# DIGITAL.net
KiCad netlist of a schematic drawn in Altium Designer
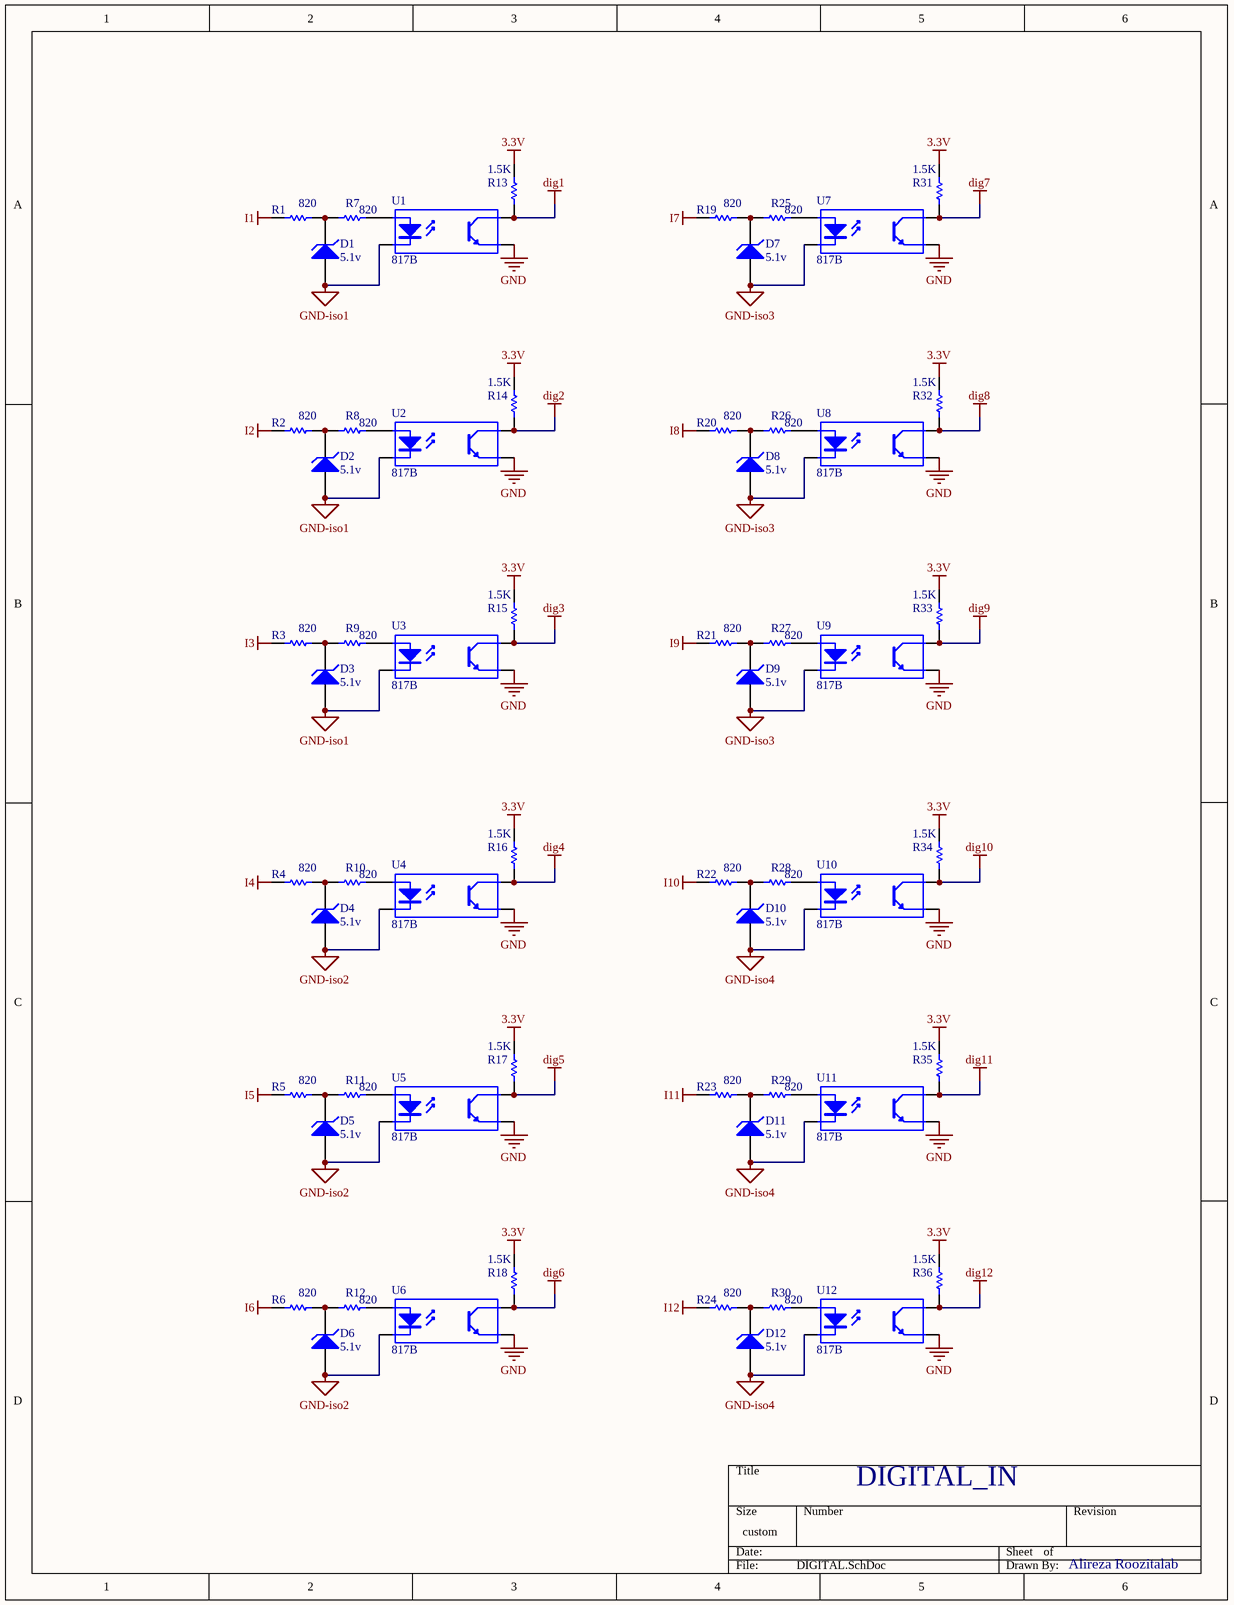
[diagram p0: DIGITAL.SchDoc]

(export (version "E")
  (design (tool "Eeschema 10.0.6"))
  (components
    (comp (ref "D1")
      (value "5.1v")
      (footprint "Diode-1n4148 - SMD PAD")
      (description "Zener Diode")
      (fields (field (name "PUBLISHER") "Altium Limited"))
      (libsource (lib "Miscellaneous Devices") (part "D Zener"))
    )
    (comp (ref "D2")
      (value "5.1v")
      (footprint "Diode-1n4148 - SMD PAD")
      (description "Zener Diode")
      (fields (field (name "PUBLISHER") "Altium Limited"))
      (libsource (lib "Miscellaneous Devices") (part "D Zener"))
    )
    (comp (ref "D3")
      (value "5.1v")
      (footprint "Diode-1n4148 - SMD PAD")
      (description "Zener Diode")
      (fields (field (name "PUBLISHER") "Altium Limited"))
      (libsource (lib "Miscellaneous Devices") (part "D Zener"))
    )
    (comp (ref "D4")
      (value "5.1v")
      (footprint "Diode-1n4148 - SMD PAD")
      (description "Zener Diode")
      (fields (field (name "PUBLISHER") "Altium Limited"))
      (libsource (lib "Miscellaneous Devices") (part "D Zener"))
    )
    (comp (ref "D5")
      (value "5.1v")
      (footprint "Diode-1n4148 - SMD PAD")
      (description "Zener Diode")
      (fields (field (name "PUBLISHER") "Altium Limited"))
      (libsource (lib "Miscellaneous Devices") (part "D Zener"))
    )
    (comp (ref "D6")
      (value "5.1v")
      (footprint "Diode-1n4148 - SMD PAD")
      (description "Zener Diode")
      (fields (field (name "PUBLISHER") "Altium Limited"))
      (libsource (lib "Miscellaneous Devices") (part "D Zener"))
    )
    (comp (ref "D7")
      (value "5.1v")
      (footprint "Diode-1n4148 - SMD PAD")
      (description "Zener Diode")
      (fields (field (name "PUBLISHER") "Altium Limited"))
      (libsource (lib "Miscellaneous Devices") (part "D Zener"))
    )
    (comp (ref "D8")
      (value "5.1v")
      (footprint "Diode-1n4148 - SMD PAD")
      (description "Zener Diode")
      (fields (field (name "PUBLISHER") "Altium Limited"))
      (libsource (lib "Miscellaneous Devices") (part "D Zener"))
    )
    (comp (ref "D9")
      (value "5.1v")
      (footprint "Diode-1n4148 - SMD PAD")
      (description "Zener Diode")
      (fields (field (name "PUBLISHER") "Altium Limited"))
      (libsource (lib "Miscellaneous Devices") (part "D Zener"))
    )
    (comp (ref "D10")
      (value "5.1v")
      (footprint "Diode-1n4148 - SMD PAD")
      (description "Zener Diode")
      (fields (field (name "PUBLISHER") "Altium Limited"))
      (libsource (lib "Miscellaneous Devices") (part "D Zener"))
    )
    (comp (ref "D11")
      (value "5.1v")
      (footprint "Diode-1n4148 - SMD PAD")
      (description "Zener Diode")
      (fields (field (name "PUBLISHER") "Altium Limited"))
      (libsource (lib "Miscellaneous Devices") (part "D Zener"))
    )
    (comp (ref "D12")
      (value "5.1v")
      (footprint "Diode-1n4148 - SMD PAD")
      (description "Zener Diode")
      (fields (field (name "PUBLISHER") "Altium Limited"))
      (libsource (lib "Miscellaneous Devices") (part "D Zener"))
    )
    (comp (ref "R1")
      (value "820")
      (footprint "RES 1206 (3216X08L)")
      (description "Semiconductor Resistor")
      (fields (field (name "Comment") "Res Semi") (field (name "PUBLISHER") "Altium Limited"))
      (libsource (lib "Miscellaneous Devices") (part "Res Semi"))
    )
    (comp (ref "R2")
      (value "820")
      (footprint "RES 1206 (3216X08L)")
      (description "Semiconductor Resistor")
      (fields (field (name "Comment") "Res Semi") (field (name "PUBLISHER") "Altium Limited"))
      (libsource (lib "Miscellaneous Devices") (part "Res Semi"))
    )
    (comp (ref "R3")
      (value "820")
      (footprint "RES 1206 (3216X08L)")
      (description "Semiconductor Resistor")
      (fields (field (name "Comment") "Res Semi") (field (name "PUBLISHER") "Altium Limited"))
      (libsource (lib "Miscellaneous Devices") (part "Res Semi"))
    )
    (comp (ref "R4")
      (value "820")
      (footprint "RES 1206 (3216X08L)")
      (description "Semiconductor Resistor")
      (fields (field (name "Comment") "Res Semi") (field (name "PUBLISHER") "Altium Limited"))
      (libsource (lib "Miscellaneous Devices") (part "Res Semi"))
    )
    (comp (ref "R5")
      (value "820")
      (footprint "RES 1206 (3216X08L)")
      (description "Semiconductor Resistor")
      (fields (field (name "Comment") "Res Semi") (field (name "PUBLISHER") "Altium Limited"))
      (libsource (lib "Miscellaneous Devices") (part "Res Semi"))
    )
    (comp (ref "R6")
      (value "820")
      (footprint "RES 1206 (3216X08L)")
      (description "Semiconductor Resistor")
      (fields (field (name "Comment") "Res Semi") (field (name "PUBLISHER") "Altium Limited"))
      (libsource (lib "Miscellaneous Devices") (part "Res Semi"))
    )
    (comp (ref "R7")
      (value "820")
      (footprint "RES 1206 (3216X08L)")
      (description "Semiconductor Resistor")
      (fields (field (name "Comment") "Res Semi") (field (name "PUBLISHER") "Altium Limited"))
      (libsource (lib "Miscellaneous Devices") (part "Res Semi"))
    )
    (comp (ref "R8")
      (value "820")
      (footprint "RES 1206 (3216X08L)")
      (description "Semiconductor Resistor")
      (fields (field (name "Comment") "Res Semi") (field (name "PUBLISHER") "Altium Limited"))
      (libsource (lib "Miscellaneous Devices") (part "Res Semi"))
    )
    (comp (ref "R9")
      (value "820")
      (footprint "RES 1206 (3216X08L)")
      (description "Semiconductor Resistor")
      (fields (field (name "Comment") "Res Semi") (field (name "PUBLISHER") "Altium Limited"))
      (libsource (lib "Miscellaneous Devices") (part "Res Semi"))
    )
    (comp (ref "R10")
      (value "820")
      (footprint "RES 1206 (3216X08L)")
      (description "Semiconductor Resistor")
      (fields (field (name "Comment") "Res Semi") (field (name "PUBLISHER") "Altium Limited"))
      (libsource (lib "Miscellaneous Devices") (part "Res Semi"))
    )
    (comp (ref "R11")
      (value "820")
      (footprint "RES 1206 (3216X08L)")
      (description "Semiconductor Resistor")
      (fields (field (name "Comment") "Res Semi") (field (name "PUBLISHER") "Altium Limited"))
      (libsource (lib "Miscellaneous Devices") (part "Res Semi"))
    )
    (comp (ref "R12")
      (value "820")
      (footprint "RES 1206 (3216X08L)")
      (description "Semiconductor Resistor")
      (fields (field (name "Comment") "Res Semi") (field (name "PUBLISHER") "Altium Limited"))
      (libsource (lib "Miscellaneous Devices") (part "Res Semi"))
    )
    (comp (ref "R13")
      (value "1.5K")
      (footprint "RES 1206 (3216X08L)")
      (description "Semiconductor Resistor")
      (fields (field (name "Comment") "Res Semi") (field (name "PUBLISHER") "Altium Limited"))
      (libsource (lib "Miscellaneous Devices") (part "Res Semi"))
    )
    (comp (ref "R14")
      (value "1.5K")
      (footprint "RES 1206 (3216X08L)")
      (description "Semiconductor Resistor")
      (fields (field (name "Comment") "Res Semi") (field (name "PUBLISHER") "Altium Limited"))
      (libsource (lib "Miscellaneous Devices") (part "Res Semi"))
    )
    (comp (ref "R15")
      (value "1.5K")
      (footprint "RES 1206 (3216X08L)")
      (description "Semiconductor Resistor")
      (fields (field (name "Comment") "Res Semi") (field (name "PUBLISHER") "Altium Limited"))
      (libsource (lib "Miscellaneous Devices") (part "Res Semi"))
    )
    (comp (ref "R16")
      (value "1.5K")
      (footprint "RES 1206 (3216X08L)")
      (description "Semiconductor Resistor")
      (fields (field (name "Comment") "Res Semi") (field (name "PUBLISHER") "Altium Limited"))
      (libsource (lib "Miscellaneous Devices") (part "Res Semi"))
    )
    (comp (ref "R17")
      (value "1.5K")
      (footprint "RES 1206 (3216X08L)")
      (description "Semiconductor Resistor")
      (fields (field (name "Comment") "Res Semi") (field (name "PUBLISHER") "Altium Limited"))
      (libsource (lib "Miscellaneous Devices") (part "Res Semi"))
    )
    (comp (ref "R18")
      (value "1.5K")
      (footprint "RES 1206 (3216X08L)")
      (description "Semiconductor Resistor")
      (fields (field (name "Comment") "Res Semi") (field (name "PUBLISHER") "Altium Limited"))
      (libsource (lib "Miscellaneous Devices") (part "Res Semi"))
    )
    (comp (ref "R19")
      (value "820")
      (footprint "RES 1206 (3216X08L)")
      (description "Semiconductor Resistor")
      (fields (field (name "Comment") "Res Semi") (field (name "PUBLISHER") "Altium Limited"))
      (libsource (lib "Miscellaneous Devices") (part "Res Semi"))
    )
    (comp (ref "R20")
      (value "820")
      (footprint "RES 1206 (3216X08L)")
      (description "Semiconductor Resistor")
      (fields (field (name "Comment") "Res Semi") (field (name "PUBLISHER") "Altium Limited"))
      (libsource (lib "Miscellaneous Devices") (part "Res Semi"))
    )
    (comp (ref "R21")
      (value "820")
      (footprint "RES 1206 (3216X08L)")
      (description "Semiconductor Resistor")
      (fields (field (name "Comment") "Res Semi") (field (name "PUBLISHER") "Altium Limited"))
      (libsource (lib "Miscellaneous Devices") (part "Res Semi"))
    )
    (comp (ref "R22")
      (value "820")
      (footprint "RES 1206 (3216X08L)")
      (description "Semiconductor Resistor")
      (fields (field (name "Comment") "Res Semi") (field (name "PUBLISHER") "Altium Limited"))
      (libsource (lib "Miscellaneous Devices") (part "Res Semi"))
    )
    (comp (ref "R23")
      (value "820")
      (footprint "RES 1206 (3216X08L)")
      (description "Semiconductor Resistor")
      (fields (field (name "Comment") "Res Semi") (field (name "PUBLISHER") "Altium Limited"))
      (libsource (lib "Miscellaneous Devices") (part "Res Semi"))
    )
    (comp (ref "R24")
      (value "820")
      (footprint "RES 1206 (3216X08L)")
      (description "Semiconductor Resistor")
      (fields (field (name "Comment") "Res Semi") (field (name "PUBLISHER") "Altium Limited"))
      (libsource (lib "Miscellaneous Devices") (part "Res Semi"))
    )
    (comp (ref "R25")
      (value "820")
      (footprint "RES 1206 (3216X08L)")
      (description "Semiconductor Resistor")
      (fields (field (name "Comment") "Res Semi") (field (name "PUBLISHER") "Altium Limited"))
      (libsource (lib "Miscellaneous Devices") (part "Res Semi"))
    )
    (comp (ref "R26")
      (value "820")
      (footprint "RES 1206 (3216X08L)")
      (description "Semiconductor Resistor")
      (fields (field (name "Comment") "Res Semi") (field (name "PUBLISHER") "Altium Limited"))
      (libsource (lib "Miscellaneous Devices") (part "Res Semi"))
    )
    (comp (ref "R27")
      (value "820")
      (footprint "RES 1206 (3216X08L)")
      (description "Semiconductor Resistor")
      (fields (field (name "Comment") "Res Semi") (field (name "PUBLISHER") "Altium Limited"))
      (libsource (lib "Miscellaneous Devices") (part "Res Semi"))
    )
    (comp (ref "R28")
      (value "820")
      (footprint "RES 1206 (3216X08L)")
      (description "Semiconductor Resistor")
      (fields (field (name "Comment") "Res Semi") (field (name "PUBLISHER") "Altium Limited"))
      (libsource (lib "Miscellaneous Devices") (part "Res Semi"))
    )
    (comp (ref "R29")
      (value "820")
      (footprint "RES 1206 (3216X08L)")
      (description "Semiconductor Resistor")
      (fields (field (name "Comment") "Res Semi") (field (name "PUBLISHER") "Altium Limited"))
      (libsource (lib "Miscellaneous Devices") (part "Res Semi"))
    )
    (comp (ref "R30")
      (value "820")
      (footprint "RES 1206 (3216X08L)")
      (description "Semiconductor Resistor")
      (fields (field (name "Comment") "Res Semi") (field (name "PUBLISHER") "Altium Limited"))
      (libsource (lib "Miscellaneous Devices") (part "Res Semi"))
    )
    (comp (ref "R31")
      (value "1.5K")
      (footprint "RES 1206 (3216X08L)")
      (description "Semiconductor Resistor")
      (fields (field (name "Comment") "Res Semi") (field (name "PUBLISHER") "Altium Limited"))
      (libsource (lib "Miscellaneous Devices") (part "Res Semi"))
    )
    (comp (ref "R32")
      (value "1.5K")
      (footprint "RES 1206 (3216X08L)")
      (description "Semiconductor Resistor")
      (fields (field (name "Comment") "Res Semi") (field (name "PUBLISHER") "Altium Limited"))
      (libsource (lib "Miscellaneous Devices") (part "Res Semi"))
    )
    (comp (ref "R33")
      (value "1.5K")
      (footprint "RES 1206 (3216X08L)")
      (description "Semiconductor Resistor")
      (fields (field (name "Comment") "Res Semi") (field (name "PUBLISHER") "Altium Limited"))
      (libsource (lib "Miscellaneous Devices") (part "Res Semi"))
    )
    (comp (ref "R34")
      (value "1.5K")
      (footprint "RES 1206 (3216X08L)")
      (description "Semiconductor Resistor")
      (fields (field (name "Comment") "Res Semi") (field (name "PUBLISHER") "Altium Limited"))
      (libsource (lib "Miscellaneous Devices") (part "Res Semi"))
    )
    (comp (ref "R35")
      (value "1.5K")
      (footprint "RES 1206 (3216X08L)")
      (description "Semiconductor Resistor")
      (fields (field (name "Comment") "Res Semi") (field (name "PUBLISHER") "Altium Limited"))
      (libsource (lib "Miscellaneous Devices") (part "Res Semi"))
    )
    (comp (ref "R36")
      (value "1.5K")
      (footprint "RES 1206 (3216X08L)")
      (description "Semiconductor Resistor")
      (fields (field (name "Comment") "Res Semi") (field (name "PUBLISHER") "Altium Limited"))
      (libsource (lib "Miscellaneous Devices") (part "Res Semi"))
    )
    (comp (ref "U1")
      (value "817B")
      (footprint "DIP+4")
      (description "4-Pin Phototransistor Optocoupler")
      (fields (field (name "PUBLISHER") "Altium Limited"))
      (libsource (lib "Miscellaneous Devices") (part "Optoisolator1"))
    )
    (comp (ref "U2")
      (value "817B")
      (footprint "DIP+4")
      (description "4-Pin Phototransistor Optocoupler")
      (fields (field (name "PUBLISHER") "Altium Limited"))
      (libsource (lib "Miscellaneous Devices") (part "Optoisolator1"))
    )
    (comp (ref "U3")
      (value "817B")
      (footprint "DIP+4")
      (description "4-Pin Phototransistor Optocoupler")
      (fields (field (name "PUBLISHER") "Altium Limited"))
      (libsource (lib "Miscellaneous Devices") (part "Optoisolator1"))
    )
    (comp (ref "U4")
      (value "817B")
      (footprint "DIP+4")
      (description "4-Pin Phototransistor Optocoupler")
      (fields (field (name "PUBLISHER") "Altium Limited"))
      (libsource (lib "Miscellaneous Devices") (part "Optoisolator1"))
    )
    (comp (ref "U5")
      (value "817B")
      (footprint "DIP+4")
      (description "4-Pin Phototransistor Optocoupler")
      (fields (field (name "PUBLISHER") "Altium Limited"))
      (libsource (lib "Miscellaneous Devices") (part "Optoisolator1"))
    )
    (comp (ref "U6")
      (value "817B")
      (footprint "DIP+4")
      (description "4-Pin Phototransistor Optocoupler")
      (fields (field (name "PUBLISHER") "Altium Limited"))
      (libsource (lib "Miscellaneous Devices") (part "Optoisolator1"))
    )
    (comp (ref "U7")
      (value "817B")
      (footprint "DIP+4")
      (description "4-Pin Phototransistor Optocoupler")
      (fields (field (name "PUBLISHER") "Altium Limited"))
      (libsource (lib "Miscellaneous Devices") (part "Optoisolator1"))
    )
    (comp (ref "U8")
      (value "817B")
      (footprint "DIP+4")
      (description "4-Pin Phototransistor Optocoupler")
      (fields (field (name "PUBLISHER") "Altium Limited"))
      (libsource (lib "Miscellaneous Devices") (part "Optoisolator1"))
    )
    (comp (ref "U9")
      (value "817B")
      (footprint "DIP+4")
      (description "4-Pin Phototransistor Optocoupler")
      (fields (field (name "PUBLISHER") "Altium Limited"))
      (libsource (lib "Miscellaneous Devices") (part "Optoisolator1"))
    )
    (comp (ref "U10")
      (value "817B")
      (footprint "DIP+4")
      (description "4-Pin Phototransistor Optocoupler")
      (fields (field (name "PUBLISHER") "Altium Limited"))
      (libsource (lib "Miscellaneous Devices") (part "Optoisolator1"))
    )
    (comp (ref "U11")
      (value "817B")
      (footprint "DIP+4")
      (description "4-Pin Phototransistor Optocoupler")
      (fields (field (name "PUBLISHER") "Altium Limited"))
      (libsource (lib "Miscellaneous Devices") (part "Optoisolator1"))
    )
    (comp (ref "U12")
      (value "817B")
      (footprint "DIP+4")
      (description "4-Pin Phototransistor Optocoupler")
      (fields (field (name "PUBLISHER") "Altium Limited"))
      (libsource (lib "Miscellaneous Devices") (part "Optoisolator1"))
    )
  )
  (nets
    (net (code "1") (name "3.3V") (class "Default")
      (node (ref "R13") (pin "2") (pinfunction "2_2") (pintype "passive"))
      (node (ref "R14") (pin "2") (pinfunction "2_2") (pintype "passive"))
      (node (ref "R15") (pin "2") (pinfunction "2_2") (pintype "passive"))
      (node (ref "R16") (pin "2") (pinfunction "2_2") (pintype "passive"))
      (node (ref "R17") (pin "2") (pinfunction "2_2") (pintype "passive"))
      (node (ref "R18") (pin "2") (pinfunction "2_2") (pintype "passive"))
      (node (ref "R31") (pin "2") (pinfunction "2_2") (pintype "passive"))
      (node (ref "R32") (pin "2") (pinfunction "2_2") (pintype "passive"))
      (node (ref "R33") (pin "2") (pinfunction "2_2") (pintype "passive"))
      (node (ref "R34") (pin "2") (pinfunction "2_2") (pintype "passive"))
      (node (ref "R35") (pin "2") (pinfunction "2_2") (pintype "passive"))
      (node (ref "R36") (pin "2") (pinfunction "2_2") (pintype "passive"))
    )
    (net (code "2") (name "GND") (class "Default")
      (node (ref "U1") (pin "3") (pinfunction "E_3") (pintype "passive"))
      (node (ref "U10") (pin "3") (pinfunction "E_3") (pintype "passive"))
      (node (ref "U11") (pin "3") (pinfunction "E_3") (pintype "passive"))
      (node (ref "U12") (pin "3") (pinfunction "E_3") (pintype "passive"))
      (node (ref "U2") (pin "3") (pinfunction "E_3") (pintype "passive"))
      (node (ref "U3") (pin "3") (pinfunction "E_3") (pintype "passive"))
      (node (ref "U4") (pin "3") (pinfunction "E_3") (pintype "passive"))
      (node (ref "U5") (pin "3") (pinfunction "E_3") (pintype "passive"))
      (node (ref "U6") (pin "3") (pinfunction "E_3") (pintype "passive"))
      (node (ref "U7") (pin "3") (pinfunction "E_3") (pintype "passive"))
      (node (ref "U8") (pin "3") (pinfunction "E_3") (pintype "passive"))
      (node (ref "U9") (pin "3") (pinfunction "E_3") (pintype "passive"))
    )
    (net (code "3") (name "GND-iso1") (class "Default")
      (node (ref "D1") (pin "1") (pinfunction "A_1") (pintype "passive"))
      (node (ref "D2") (pin "1") (pinfunction "A_1") (pintype "passive"))
      (node (ref "D3") (pin "1") (pinfunction "A_1") (pintype "passive"))
      (node (ref "U1") (pin "2") (pinfunction "K_2") (pintype "passive"))
      (node (ref "U2") (pin "2") (pinfunction "K_2") (pintype "passive"))
      (node (ref "U3") (pin "2") (pinfunction "K_2") (pintype "passive"))
    )
    (net (code "4") (name "GND-iso2") (class "Default")
      (node (ref "D4") (pin "1") (pinfunction "A_1") (pintype "passive"))
      (node (ref "D5") (pin "1") (pinfunction "A_1") (pintype "passive"))
      (node (ref "D6") (pin "1") (pinfunction "A_1") (pintype "passive"))
      (node (ref "U4") (pin "2") (pinfunction "K_2") (pintype "passive"))
      (node (ref "U5") (pin "2") (pinfunction "K_2") (pintype "passive"))
      (node (ref "U6") (pin "2") (pinfunction "K_2") (pintype "passive"))
    )
    (net (code "5") (name "GND-iso3") (class "Default")
      (node (ref "D7") (pin "1") (pinfunction "A_1") (pintype "passive"))
      (node (ref "D8") (pin "1") (pinfunction "A_1") (pintype "passive"))
      (node (ref "D9") (pin "1") (pinfunction "A_1") (pintype "passive"))
      (node (ref "U7") (pin "2") (pinfunction "K_2") (pintype "passive"))
      (node (ref "U8") (pin "2") (pinfunction "K_2") (pintype "passive"))
      (node (ref "U9") (pin "2") (pinfunction "K_2") (pintype "passive"))
    )
    (net (code "6") (name "GND-iso4") (class "Default")
      (node (ref "D10") (pin "1") (pinfunction "A_1") (pintype "passive"))
      (node (ref "D11") (pin "1") (pinfunction "A_1") (pintype "passive"))
      (node (ref "D12") (pin "1") (pinfunction "A_1") (pintype "passive"))
      (node (ref "U10") (pin "2") (pinfunction "K_2") (pintype "passive"))
      (node (ref "U11") (pin "2") (pinfunction "K_2") (pintype "passive"))
      (node (ref "U12") (pin "2") (pinfunction "K_2") (pintype "passive"))
    )
    (net (code "7") (name "I1") (class "Default")
      (node (ref "R1") (pin "1") (pinfunction "1_1") (pintype "passive"))
    )
    (net (code "8") (name "I2") (class "Default")
      (node (ref "R2") (pin "1") (pinfunction "1_1") (pintype "passive"))
    )
    (net (code "9") (name "I3") (class "Default")
      (node (ref "R3") (pin "1") (pinfunction "1_1") (pintype "passive"))
    )
    (net (code "10") (name "I4") (class "Default")
      (node (ref "R4") (pin "1") (pinfunction "1_1") (pintype "passive"))
    )
    (net (code "11") (name "I5") (class "Default")
      (node (ref "R5") (pin "1") (pinfunction "1_1") (pintype "passive"))
    )
    (net (code "12") (name "I6") (class "Default")
      (node (ref "R6") (pin "1") (pinfunction "1_1") (pintype "passive"))
    )
    (net (code "13") (name "I7") (class "Default")
      (node (ref "R19") (pin "1") (pinfunction "1_1") (pintype "passive"))
    )
    (net (code "14") (name "I8") (class "Default")
      (node (ref "R20") (pin "1") (pinfunction "1_1") (pintype "passive"))
    )
    (net (code "15") (name "I9") (class "Default")
      (node (ref "R21") (pin "1") (pinfunction "1_1") (pintype "passive"))
    )
    (net (code "16") (name "I10") (class "Default")
      (node (ref "R22") (pin "1") (pinfunction "1_1") (pintype "passive"))
    )
    (net (code "17") (name "I11") (class "Default")
      (node (ref "R23") (pin "1") (pinfunction "1_1") (pintype "passive"))
    )
    (net (code "18") (name "I12") (class "Default")
      (node (ref "R24") (pin "1") (pinfunction "1_1") (pintype "passive"))
    )
    (net (code "19") (name "Net-(D1-K)") (class "Default")
      (node (ref "D1") (pin "2") (pinfunction "K_2") (pintype "passive"))
      (node (ref "R1") (pin "2") (pinfunction "2_2") (pintype "passive"))
      (node (ref "R7") (pin "1") (pinfunction "1_1") (pintype "passive"))
    )
    (net (code "20") (name "Net-(D2-K)") (class "Default")
      (node (ref "D2") (pin "2") (pinfunction "K_2") (pintype "passive"))
      (node (ref "R2") (pin "2") (pinfunction "2_2") (pintype "passive"))
      (node (ref "R8") (pin "1") (pinfunction "1_1") (pintype "passive"))
    )
    (net (code "21") (name "Net-(D3-K)") (class "Default")
      (node (ref "D3") (pin "2") (pinfunction "K_2") (pintype "passive"))
      (node (ref "R3") (pin "2") (pinfunction "2_2") (pintype "passive"))
      (node (ref "R9") (pin "1") (pinfunction "1_1") (pintype "passive"))
    )
    (net (code "22") (name "Net-(D4-K)") (class "Default")
      (node (ref "D4") (pin "2") (pinfunction "K_2") (pintype "passive"))
      (node (ref "R10") (pin "1") (pinfunction "1_1") (pintype "passive"))
      (node (ref "R4") (pin "2") (pinfunction "2_2") (pintype "passive"))
    )
    (net (code "23") (name "Net-(D5-K)") (class "Default")
      (node (ref "D5") (pin "2") (pinfunction "K_2") (pintype "passive"))
      (node (ref "R11") (pin "1") (pinfunction "1_1") (pintype "passive"))
      (node (ref "R5") (pin "2") (pinfunction "2_2") (pintype "passive"))
    )
    (net (code "24") (name "Net-(D6-K)") (class "Default")
      (node (ref "D6") (pin "2") (pinfunction "K_2") (pintype "passive"))
      (node (ref "R12") (pin "1") (pinfunction "1_1") (pintype "passive"))
      (node (ref "R6") (pin "2") (pinfunction "2_2") (pintype "passive"))
    )
    (net (code "25") (name "Net-(D7-K)") (class "Default")
      (node (ref "D7") (pin "2") (pinfunction "K_2") (pintype "passive"))
      (node (ref "R19") (pin "2") (pinfunction "2_2") (pintype "passive"))
      (node (ref "R25") (pin "1") (pinfunction "1_1") (pintype "passive"))
    )
    (net (code "26") (name "Net-(D8-K)") (class "Default")
      (node (ref "D8") (pin "2") (pinfunction "K_2") (pintype "passive"))
      (node (ref "R20") (pin "2") (pinfunction "2_2") (pintype "passive"))
      (node (ref "R26") (pin "1") (pinfunction "1_1") (pintype "passive"))
    )
    (net (code "27") (name "Net-(D9-K)") (class "Default")
      (node (ref "D9") (pin "2") (pinfunction "K_2") (pintype "passive"))
      (node (ref "R21") (pin "2") (pinfunction "2_2") (pintype "passive"))
      (node (ref "R27") (pin "1") (pinfunction "1_1") (pintype "passive"))
    )
    (net (code "28") (name "Net-(D10-K)") (class "Default")
      (node (ref "D10") (pin "2") (pinfunction "K_2") (pintype "passive"))
      (node (ref "R22") (pin "2") (pinfunction "2_2") (pintype "passive"))
      (node (ref "R28") (pin "1") (pinfunction "1_1") (pintype "passive"))
    )
    (net (code "29") (name "Net-(D11-K)") (class "Default")
      (node (ref "D11") (pin "2") (pinfunction "K_2") (pintype "passive"))
      (node (ref "R23") (pin "2") (pinfunction "2_2") (pintype "passive"))
      (node (ref "R29") (pin "1") (pinfunction "1_1") (pintype "passive"))
    )
    (net (code "30") (name "Net-(D12-K)") (class "Default")
      (node (ref "D12") (pin "2") (pinfunction "K_2") (pintype "passive"))
      (node (ref "R24") (pin "2") (pinfunction "2_2") (pintype "passive"))
      (node (ref "R30") (pin "1") (pinfunction "1_1") (pintype "passive"))
    )
    (net (code "31") (name "Net-(U1-A)") (class "Default")
      (node (ref "R7") (pin "2") (pinfunction "2_2") (pintype "passive"))
      (node (ref "U1") (pin "1") (pinfunction "A_1") (pintype "passive"))
    )
    (net (code "32") (name "Net-(U2-A)") (class "Default")
      (node (ref "R8") (pin "2") (pinfunction "2_2") (pintype "passive"))
      (node (ref "U2") (pin "1") (pinfunction "A_1") (pintype "passive"))
    )
    (net (code "33") (name "Net-(U3-A)") (class "Default")
      (node (ref "R9") (pin "2") (pinfunction "2_2") (pintype "passive"))
      (node (ref "U3") (pin "1") (pinfunction "A_1") (pintype "passive"))
    )
    (net (code "34") (name "Net-(U4-A)") (class "Default")
      (node (ref "R10") (pin "2") (pinfunction "2_2") (pintype "passive"))
      (node (ref "U4") (pin "1") (pinfunction "A_1") (pintype "passive"))
    )
    (net (code "35") (name "Net-(U5-A)") (class "Default")
      (node (ref "R11") (pin "2") (pinfunction "2_2") (pintype "passive"))
      (node (ref "U5") (pin "1") (pinfunction "A_1") (pintype "passive"))
    )
    (net (code "36") (name "Net-(U6-A)") (class "Default")
      (node (ref "R12") (pin "2") (pinfunction "2_2") (pintype "passive"))
      (node (ref "U6") (pin "1") (pinfunction "A_1") (pintype "passive"))
    )
    (net (code "37") (name "Net-(U7-A)") (class "Default")
      (node (ref "R25") (pin "2") (pinfunction "2_2") (pintype "passive"))
      (node (ref "U7") (pin "1") (pinfunction "A_1") (pintype "passive"))
    )
    (net (code "38") (name "Net-(U8-A)") (class "Default")
      (node (ref "R26") (pin "2") (pinfunction "2_2") (pintype "passive"))
      (node (ref "U8") (pin "1") (pinfunction "A_1") (pintype "passive"))
    )
    (net (code "39") (name "Net-(U9-A)") (class "Default")
      (node (ref "R27") (pin "2") (pinfunction "2_2") (pintype "passive"))
      (node (ref "U9") (pin "1") (pinfunction "A_1") (pintype "passive"))
    )
    (net (code "40") (name "Net-(U10-A)") (class "Default")
      (node (ref "R28") (pin "2") (pinfunction "2_2") (pintype "passive"))
      (node (ref "U10") (pin "1") (pinfunction "A_1") (pintype "passive"))
    )
    (net (code "41") (name "Net-(U11-A)") (class "Default")
      (node (ref "R29") (pin "2") (pinfunction "2_2") (pintype "passive"))
      (node (ref "U11") (pin "1") (pinfunction "A_1") (pintype "passive"))
    )
    (net (code "42") (name "Net-(U12-A)") (class "Default")
      (node (ref "R30") (pin "2") (pinfunction "2_2") (pintype "passive"))
      (node (ref "U12") (pin "1") (pinfunction "A_1") (pintype "passive"))
    )
    (net (code "43") (name "dig1") (class "Default")
      (node (ref "R13") (pin "1") (pinfunction "1_1") (pintype "passive"))
      (node (ref "U1") (pin "4") (pinfunction "C_4") (pintype "passive"))
    )
    (net (code "44") (name "dig2") (class "Default")
      (node (ref "R14") (pin "1") (pinfunction "1_1") (pintype "passive"))
      (node (ref "U2") (pin "4") (pinfunction "C_4") (pintype "passive"))
    )
    (net (code "45") (name "dig3") (class "Default")
      (node (ref "R15") (pin "1") (pinfunction "1_1") (pintype "passive"))
      (node (ref "U3") (pin "4") (pinfunction "C_4") (pintype "passive"))
    )
    (net (code "46") (name "dig4") (class "Default")
      (node (ref "R16") (pin "1") (pinfunction "1_1") (pintype "passive"))
      (node (ref "U4") (pin "4") (pinfunction "C_4") (pintype "passive"))
    )
    (net (code "47") (name "dig5") (class "Default")
      (node (ref "R17") (pin "1") (pinfunction "1_1") (pintype "passive"))
      (node (ref "U5") (pin "4") (pinfunction "C_4") (pintype "passive"))
    )
    (net (code "48") (name "dig6") (class "Default")
      (node (ref "R18") (pin "1") (pinfunction "1_1") (pintype "passive"))
      (node (ref "U6") (pin "4") (pinfunction "C_4") (pintype "passive"))
    )
    (net (code "49") (name "dig7") (class "Default")
      (node (ref "R31") (pin "1") (pinfunction "1_1") (pintype "passive"))
      (node (ref "U7") (pin "4") (pinfunction "C_4") (pintype "passive"))
    )
    (net (code "50") (name "dig8") (class "Default")
      (node (ref "R32") (pin "1") (pinfunction "1_1") (pintype "passive"))
      (node (ref "U8") (pin "4") (pinfunction "C_4") (pintype "passive"))
    )
    (net (code "51") (name "dig9") (class "Default")
      (node (ref "R33") (pin "1") (pinfunction "1_1") (pintype "passive"))
      (node (ref "U9") (pin "4") (pinfunction "C_4") (pintype "passive"))
    )
    (net (code "52") (name "dig10") (class "Default")
      (node (ref "R34") (pin "1") (pinfunction "1_1") (pintype "passive"))
      (node (ref "U10") (pin "4") (pinfunction "C_4") (pintype "passive"))
    )
    (net (code "53") (name "dig11") (class "Default")
      (node (ref "R35") (pin "1") (pinfunction "1_1") (pintype "passive"))
      (node (ref "U11") (pin "4") (pinfunction "C_4") (pintype "passive"))
    )
    (net (code "54") (name "dig12") (class "Default")
      (node (ref "R36") (pin "1") (pinfunction "1_1") (pintype "passive"))
      (node (ref "U12") (pin "4") (pinfunction "C_4") (pintype "passive"))
    )
  )
)
